# Platypus_FPC.net
KiCad netlist of a schematic drawn in EAGLE
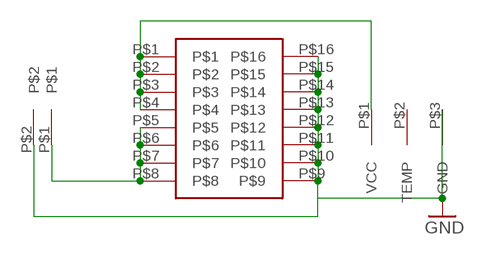
[diagram p0: schematic, sheet 1]

(export (version "E")
  (design (tool "Eeschema 10.0.6"))
  (components
    (comp (ref "U$1")
      (value "BM10B(0.8)-16DP-0.4V(51)")
      (footprint "eagle-import:16-HEADER")
      (libsource (lib "eagle-import") (part "BM10B(0.8)-16DP-0.4V(51)"))
    )
    (comp (ref "U$2")
      (value "PLATY_BAT_PAD")
      (footprint "eagle-import:FPC-6")
      (libsource (lib "eagle-import") (part "PLATY_BAT_PAD"))
    )
    (comp (ref "U$3")
      (value "PLATY_CHARGER_CON")
      (footprint "eagle-import:2-PAD")
      (libsource (lib "eagle-import") (part "PLATY_CHARGER_CON"))
    )
  )
  (nets
    (net (code "1") (name "GND") (class "Default")
      (node (ref "U$1") (pin "P$10") (pinfunction "P$10_P$10") (pintype "bidirectional"))
      (node (ref "U$1") (pin "P$11") (pinfunction "P$11_P$11") (pintype "bidirectional"))
      (node (ref "U$1") (pin "P$12") (pinfunction "P$12_P$12") (pintype "bidirectional"))
      (node (ref "U$1") (pin "P$13") (pinfunction "P$13_P$13") (pintype "bidirectional"))
      (node (ref "U$1") (pin "P$14") (pinfunction "P$14_P$14") (pintype "bidirectional"))
      (node (ref "U$1") (pin "P$15") (pinfunction "P$15_P$15") (pintype "bidirectional"))
      (node (ref "U$1") (pin "P$16") (pinfunction "P$16_P$16") (pintype "bidirectional"))
      (node (ref "U$1") (pin "P$9") (pinfunction "P$9_P$9") (pintype "bidirectional"))
      (node (ref "U$2") (pin "P$3") (pinfunction "GND_P$3") (pintype "bidirectional"))
      (node (ref "U$3") (pin "P$2") (pinfunction "P$2_P$2") (pintype "bidirectional"))
    )
    (net (code "2") (name "Net-(U$1-PadP$5)") (class "Default")
      (node (ref "U$1") (pin "P$5") (pinfunction "P$5_P$5") (pintype "bidirectional"))
      (node (ref "U$1") (pin "P$6") (pinfunction "P$6_P$6") (pintype "bidirectional"))
      (node (ref "U$1") (pin "P$7") (pinfunction "P$7_P$7") (pintype "bidirectional"))
      (node (ref "U$1") (pin "P$8") (pinfunction "P$8_P$8") (pintype "bidirectional"))
      (node (ref "U$3") (pin "P$1") (pinfunction "P$1_P$1") (pintype "bidirectional"))
    )
    (net (code "3") (name "Net-(U$2-VCC)") (class "Default")
      (node (ref "U$1") (pin "P$1") (pinfunction "P$1_P$1") (pintype "bidirectional"))
      (node (ref "U$1") (pin "P$2") (pinfunction "P$2_P$2") (pintype "bidirectional"))
      (node (ref "U$1") (pin "P$3") (pinfunction "P$3_P$3") (pintype "bidirectional"))
      (node (ref "U$1") (pin "P$4") (pinfunction "P$4_P$4") (pintype "bidirectional"))
      (node (ref "U$2") (pin "P$1") (pinfunction "VCC_P$1") (pintype "bidirectional"))
    )
    (net (code "4") (name "unconnected-(U$2-TEMP-PadP$2)") (class "Default")
      (node (ref "U$2") (pin "P$2") (pinfunction "TEMP_P$2") (pintype "bidirectional"))
    )
  )
)
